# dual-Joystick-Breakout-v1.net
KiCad netlist of a schematic drawn in EAGLE
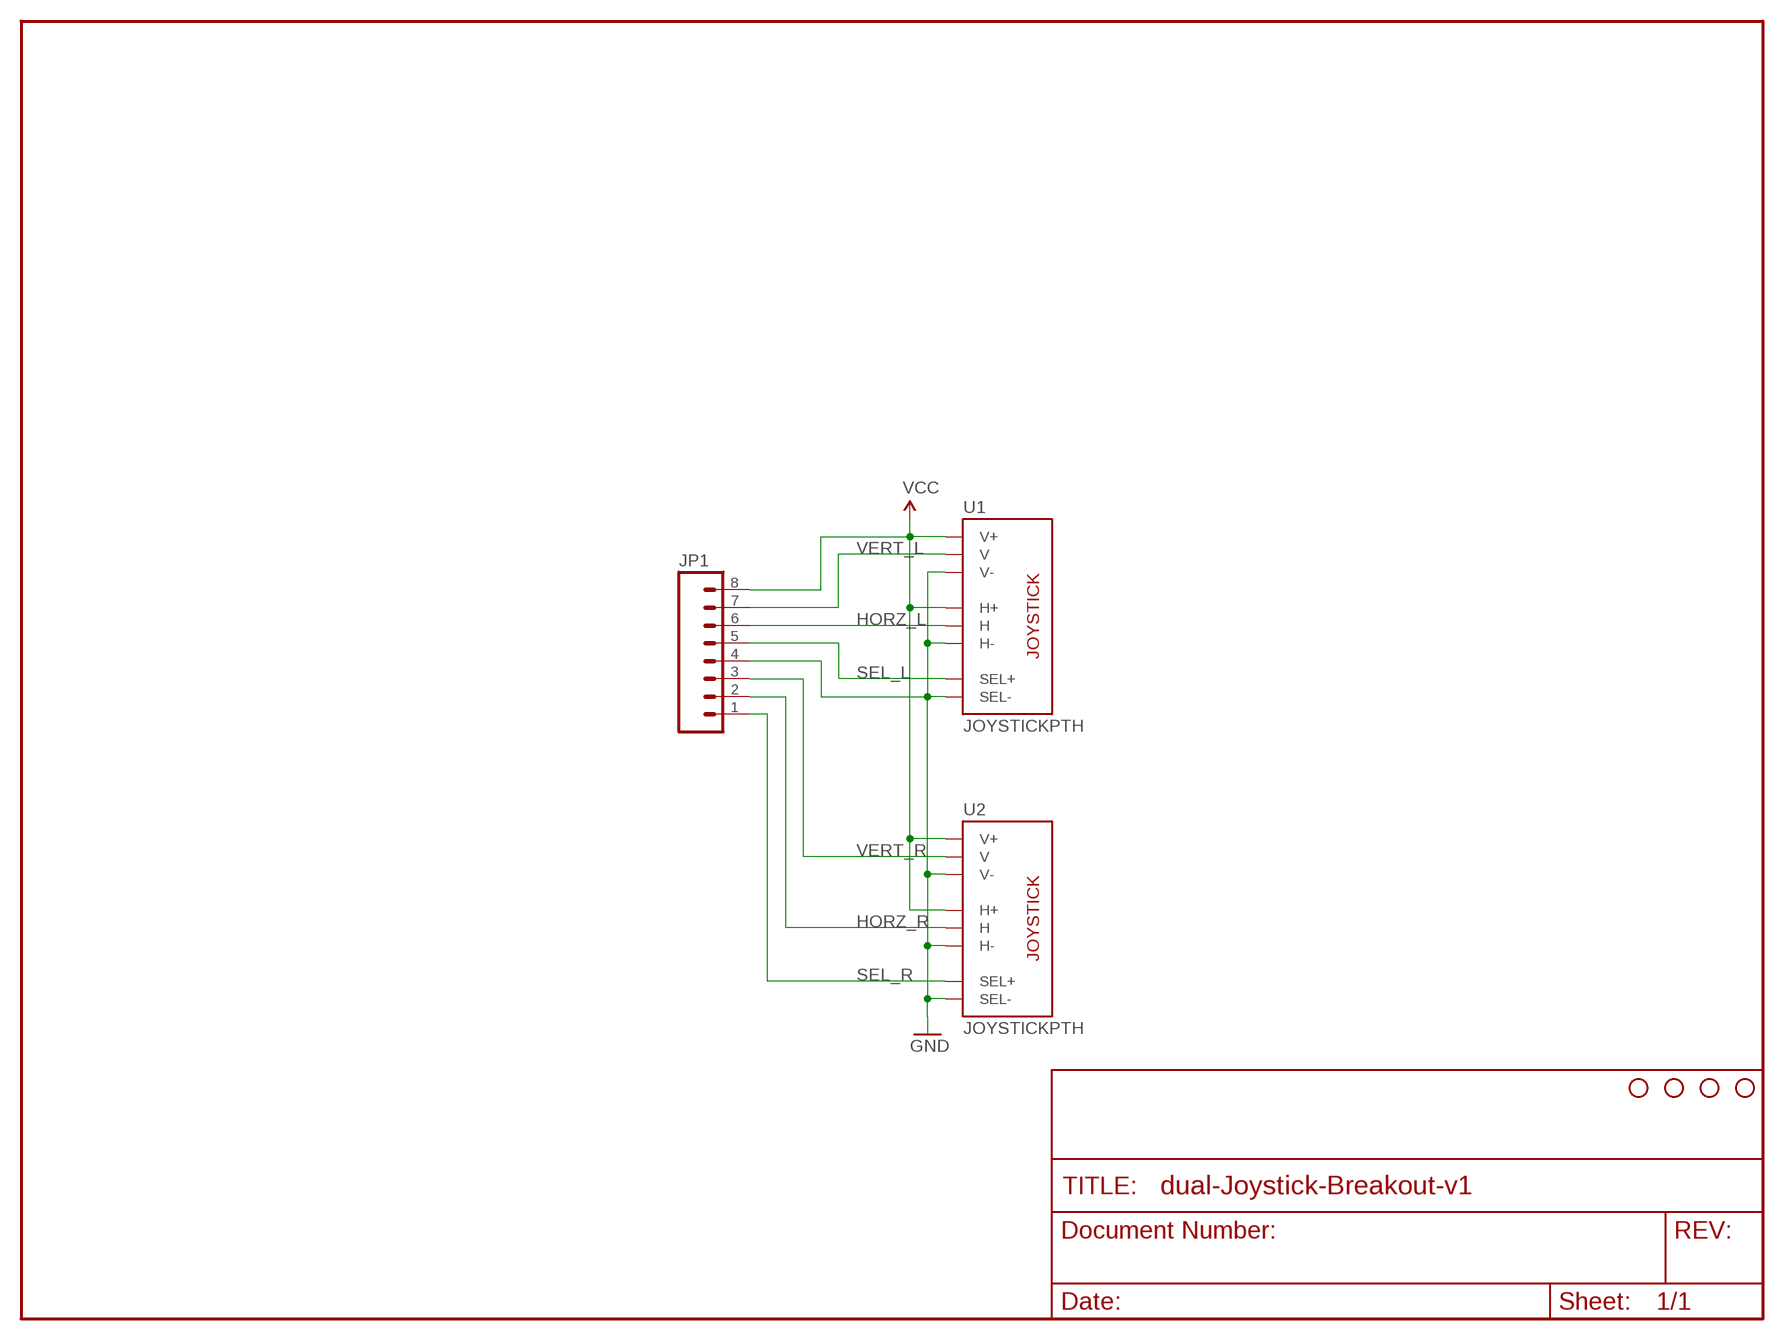
[diagram p0: schematic, sheet 1]

(export (version "E")
  (design (tool "Eeschema 10.0.6"))
  (components
    (comp (ref "JP1")
      (value "M081X08")
      (footprint "eagle-import:1X08")
      (libsource (lib "eagle-import") (part "M081X08"))
    )
    (comp (ref "U$3")
      (value "STAND-OFF")
      (footprint "eagle-import:STAND-OFF")
      (libsource (lib "eagle-import") (part "STAND-OFF"))
    )
    (comp (ref "U$4")
      (value "STAND-OFF")
      (footprint "eagle-import:STAND-OFF")
      (libsource (lib "eagle-import") (part "STAND-OFF"))
    )
    (comp (ref "U$5")
      (value "STAND-OFF")
      (footprint "eagle-import:STAND-OFF")
      (libsource (lib "eagle-import") (part "STAND-OFF"))
    )
    (comp (ref "U$6")
      (value "STAND-OFF")
      (footprint "eagle-import:STAND-OFF")
      (libsource (lib "eagle-import") (part "STAND-OFF"))
    )
    (comp (ref "U1")
      (value "JOYSTICKPTH")
      (footprint "eagle-import:JOYSTICK")
      (libsource (lib "eagle-import") (part "JOYSTICKPTH"))
    )
    (comp (ref "U2")
      (value "JOYSTICKPTH")
      (footprint "eagle-import:JOYSTICK")
      (libsource (lib "eagle-import") (part "JOYSTICKPTH"))
    )
  )
  (nets
    (net (code "1") (name "/HORZ_L") (class "Default")
      (node (ref "JP1") (pin "6") (pinfunction "6_6") (pintype "passive"))
      (node (ref "U1") (pin "H2") (pinfunction "H_H2") (pintype "bidirectional"))
    )
    (net (code "2") (name "/HORZ_R") (class "Default")
      (node (ref "JP1") (pin "2") (pinfunction "2_2") (pintype "passive"))
      (node (ref "U2") (pin "H2") (pinfunction "H_H2") (pintype "bidirectional"))
    )
    (net (code "3") (name "/SEL_L") (class "Default")
      (node (ref "JP1") (pin "5") (pinfunction "5_5") (pintype "passive"))
      (node (ref "U1") (pin "B1A") (pinfunction "SEL+_B1A") (pintype "bidirectional"))
    )
    (net (code "4") (name "/SEL_R") (class "Default")
      (node (ref "JP1") (pin "1") (pinfunction "1_1") (pintype "passive"))
      (node (ref "U2") (pin "B1A") (pinfunction "SEL+_B1A") (pintype "bidirectional"))
    )
    (net (code "5") (name "/VERT_L") (class "Default")
      (node (ref "JP1") (pin "7") (pinfunction "7_7") (pintype "passive"))
      (node (ref "U1") (pin "V2") (pinfunction "V_V2") (pintype "bidirectional"))
    )
    (net (code "6") (name "/VERT_R") (class "Default")
      (node (ref "JP1") (pin "3") (pinfunction "3_3") (pintype "passive"))
      (node (ref "U2") (pin "V2") (pinfunction "V_V2") (pintype "bidirectional"))
    )
    (net (code "7") (name "GND") (class "Default")
      (node (ref "JP1") (pin "4") (pinfunction "4_4") (pintype "passive"))
      (node (ref "U1") (pin "B2A") (pinfunction "SEL-_B2A") (pintype "bidirectional"))
      (node (ref "U1") (pin "H3") (pinfunction "H-_H3") (pintype "bidirectional"))
      (node (ref "U1") (pin "V3") (pinfunction "V-_V3") (pintype "bidirectional"))
      (node (ref "U2") (pin "B2A") (pinfunction "SEL-_B2A") (pintype "bidirectional"))
      (node (ref "U2") (pin "H3") (pinfunction "H-_H3") (pintype "bidirectional"))
      (node (ref "U2") (pin "V3") (pinfunction "V-_V3") (pintype "bidirectional"))
    )
    (net (code "8") (name "VCC") (class "Default")
      (node (ref "JP1") (pin "8") (pinfunction "8_8") (pintype "passive"))
      (node (ref "U1") (pin "H1") (pinfunction "H+_H1") (pintype "bidirectional"))
      (node (ref "U1") (pin "V1") (pinfunction "V+_V1") (pintype "bidirectional"))
      (node (ref "U2") (pin "H1") (pinfunction "H+_H1") (pintype "bidirectional"))
      (node (ref "U2") (pin "V1") (pinfunction "V+_V1") (pintype "bidirectional"))
    )
  )
)
